# PogoBoard.net
KiCad netlist of a schematic drawn in EAGLE
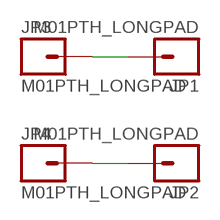
[diagram p0: schematic, sheet 1]

(export (version "E")
  (design (tool "Eeschema 10.0.6"))
  (components
    (comp (ref "JP1")
      (value "M01PTH_LONGPAD")
      (footprint "eagle-import:1X01_LONGPAD")
      (libsource (lib "eagle-import") (part "M01PTH_LONGPAD"))
    )
    (comp (ref "JP2")
      (value "M01PTH_LONGPAD")
      (footprint "eagle-import:1X01_LONGPAD")
      (libsource (lib "eagle-import") (part "M01PTH_LONGPAD"))
    )
    (comp (ref "JP3")
      (value "M01PTH_LONGPAD")
      (footprint "eagle-import:1X01_LONGPAD")
      (libsource (lib "eagle-import") (part "M01PTH_LONGPAD"))
    )
    (comp (ref "JP4")
      (value "M01PTH_LONGPAD")
      (footprint "eagle-import:1X01_LONGPAD")
      (libsource (lib "eagle-import") (part "M01PTH_LONGPAD"))
    )
  )
  (nets
    (net (code "1") (name "Net-(JP1-Pad1)") (class "Default")
      (node (ref "JP1") (pin "1") (pinfunction "1_1") (pintype "passive"))
      (node (ref "JP3") (pin "1") (pinfunction "1_1") (pintype "passive"))
    )
    (net (code "2") (name "Net-(JP2-Pad1)") (class "Default")
      (node (ref "JP2") (pin "1") (pinfunction "1_1") (pintype "passive"))
      (node (ref "JP4") (pin "1") (pinfunction "1_1") (pintype "passive"))
    )
  )
)
